# DB_Connectors.net
KiCad netlist of a schematic drawn in Altium Designer
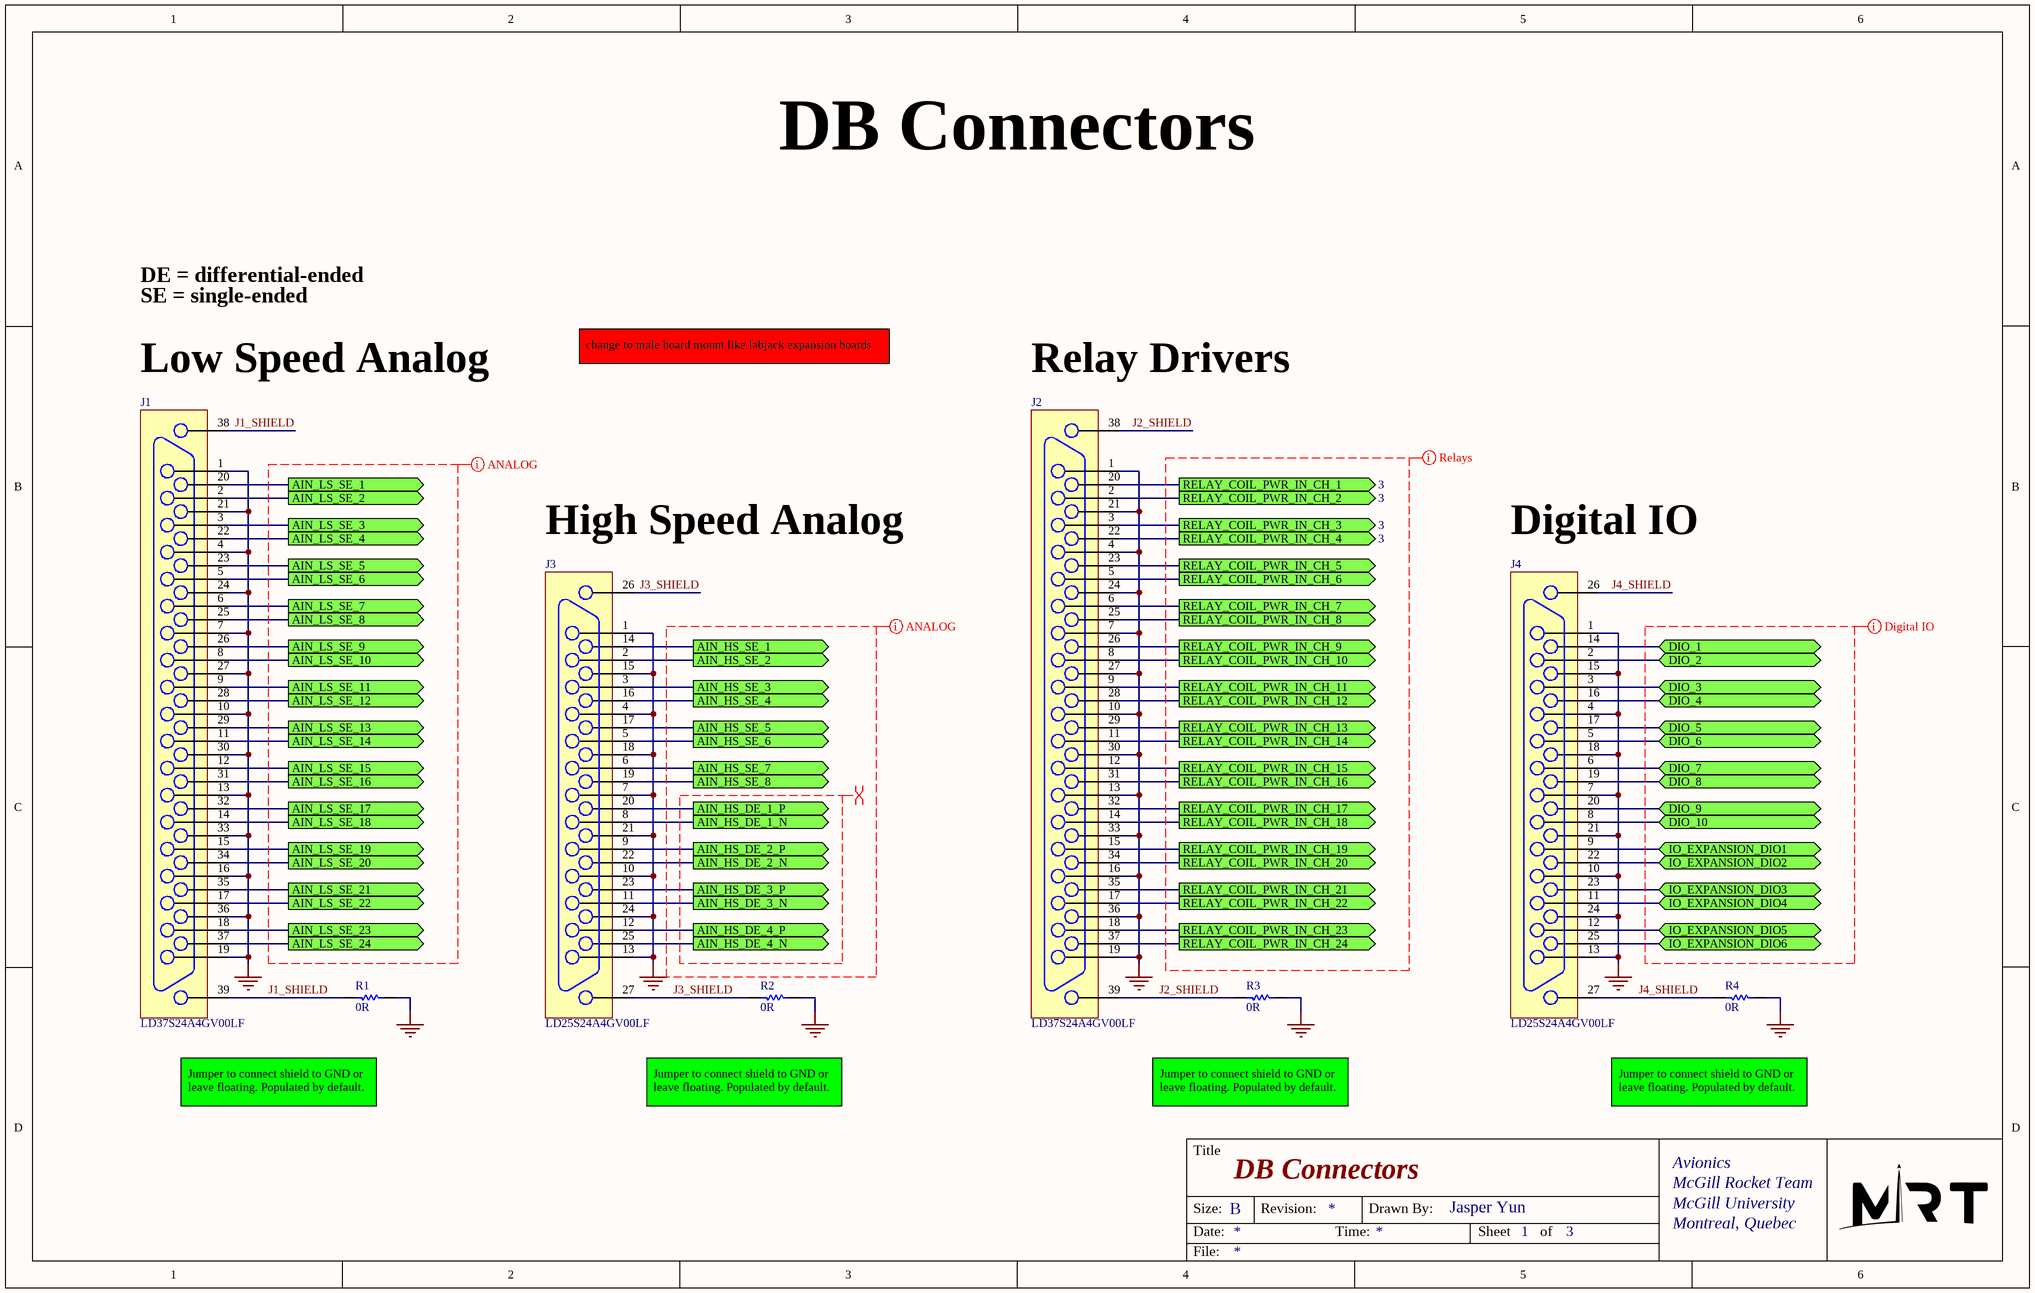
[diagram p0: DB Connectors.SchDoc]

(export (version "E")
  (design (tool "Eeschema 10.0.6"))
  (components
    (comp (ref "J1")
      (value "LD37S24A4GV00LF")
      (footprint "Connector DB37 Vertical LD37S24A4GV00LF")
      (description "DB37 LD37S24A4GV00LF (Amphenol ICC)")
      (libsource (lib "MRT SCH Library") (part "Connector DB37 (LD37S24A4GV00LF)"))
    )
    (comp (ref "J2")
      (value "LD37S24A4GV00LF")
      (footprint "Connector DB37 Vertical LD37S24A4GV00LF")
      (description "DB37 LD37S24A4GV00LF (Amphenol ICC)")
      (libsource (lib "MRT SCH Library") (part "Connector DB37 (LD37S24A4GV00LF)"))
    )
    (comp (ref "J3")
      (value "LD25S24A4GV00LF")
      (footprint "Connector DB25 Vertical LD25S24A4GV00LF")
      (description "DB25 LD25S24A4GV00LF (Amphenol ICC)")
      (libsource (lib "MRT SCH Library") (part "Connector DB25 (LD25S24A4GV00LF)"))
    )
    (comp (ref "J4")
      (value "LD25S24A4GV00LF")
      (footprint "Connector DB25 Vertical LD25S24A4GV00LF")
      (description "DB25 LD25S24A4GV00LF (Amphenol ICC)")
      (libsource (lib "MRT SCH Library") (part "Connector DB25 (LD25S24A4GV00LF)"))
    )
    (comp (ref "R1")
      (value "0R")
      (footprint "0402 RES")
      (description "Resistor")
      (fields (field (name "PUBLISHER") "Altium Limited"))
      (libsource (lib "Miscellaneous Devices") (part "Res1"))
    )
    (comp (ref "R2")
      (value "0R")
      (footprint "0402 RES")
      (description "Resistor")
      (fields (field (name "PUBLISHER") "Altium Limited"))
      (libsource (lib "Miscellaneous Devices") (part "Res1"))
    )
    (comp (ref "R3")
      (value "0R")
      (footprint "0402 RES")
      (description "Resistor")
      (fields (field (name "PUBLISHER") "Altium Limited"))
      (libsource (lib "Miscellaneous Devices") (part "Res1"))
    )
    (comp (ref "R4")
      (value "0R")
      (footprint "0402 RES")
      (description "Resistor")
      (fields (field (name "PUBLISHER") "Altium Limited"))
      (libsource (lib "Miscellaneous Devices") (part "Res1"))
    )
  )
  (nets
    (net (code "1") (name "/AIN_HS_DE_1_N") (class "Default")
      (node (ref "J3") (pin "8") (pinfunction "8_8") (pintype "passive"))
    )
    (net (code "2") (name "/AIN_HS_DE_1_P") (class "Default")
      (node (ref "J3") (pin "20") (pinfunction "20_20") (pintype "passive"))
    )
    (net (code "3") (name "/AIN_HS_DE_2_N") (class "Default")
      (node (ref "J3") (pin "22") (pinfunction "22_22") (pintype "passive"))
    )
    (net (code "4") (name "/AIN_HS_DE_2_P") (class "Default")
      (node (ref "J3") (pin "9") (pinfunction "9_9") (pintype "passive"))
    )
    (net (code "5") (name "/AIN_HS_DE_3_N") (class "Default")
      (node (ref "J3") (pin "11") (pinfunction "11_11") (pintype "passive"))
    )
    (net (code "6") (name "/AIN_HS_DE_3_P") (class "Default")
      (node (ref "J3") (pin "23") (pinfunction "23_23") (pintype "passive"))
    )
    (net (code "7") (name "/AIN_HS_DE_4_N") (class "Default")
      (node (ref "J3") (pin "25") (pinfunction "25_25") (pintype "passive"))
    )
    (net (code "8") (name "/AIN_HS_DE_4_P") (class "Default")
      (node (ref "J3") (pin "12") (pinfunction "12_12") (pintype "passive"))
    )
    (net (code "9") (name "/AIN_HS_SE_1") (class "Default")
      (node (ref "J3") (pin "14") (pinfunction "14_14") (pintype "passive"))
    )
    (net (code "10") (name "/AIN_HS_SE_2") (class "Default")
      (node (ref "J3") (pin "2") (pinfunction "2_2") (pintype "passive"))
    )
    (net (code "11") (name "/AIN_HS_SE_3") (class "Default")
      (node (ref "J3") (pin "3") (pinfunction "3_3") (pintype "passive"))
    )
    (net (code "12") (name "/AIN_HS_SE_4") (class "Default")
      (node (ref "J3") (pin "16") (pinfunction "16_16") (pintype "passive"))
    )
    (net (code "13") (name "/AIN_HS_SE_5") (class "Default")
      (node (ref "J3") (pin "17") (pinfunction "17_17") (pintype "passive"))
    )
    (net (code "14") (name "/AIN_HS_SE_6") (class "Default")
      (node (ref "J3") (pin "5") (pinfunction "5_5") (pintype "passive"))
    )
    (net (code "15") (name "/AIN_HS_SE_7") (class "Default")
      (node (ref "J3") (pin "6") (pinfunction "6_6") (pintype "passive"))
    )
    (net (code "16") (name "/AIN_HS_SE_8") (class "Default")
      (node (ref "J3") (pin "19") (pinfunction "19_19") (pintype "passive"))
    )
    (net (code "17") (name "/AIN_LS_SE_1") (class "Default")
      (node (ref "J1") (pin "20") (pinfunction "20_20") (pintype "passive"))
    )
    (net (code "18") (name "/AIN_LS_SE_2") (class "Default")
      (node (ref "J1") (pin "2") (pinfunction "2_2") (pintype "passive"))
    )
    (net (code "19") (name "/AIN_LS_SE_3") (class "Default")
      (node (ref "J1") (pin "3") (pinfunction "3_3") (pintype "passive"))
    )
    (net (code "20") (name "/AIN_LS_SE_4") (class "Default")
      (node (ref "J1") (pin "22") (pinfunction "22_22") (pintype "passive"))
    )
    (net (code "21") (name "/AIN_LS_SE_5") (class "Default")
      (node (ref "J1") (pin "23") (pinfunction "23_23") (pintype "passive"))
    )
    (net (code "22") (name "/AIN_LS_SE_6") (class "Default")
      (node (ref "J1") (pin "5") (pinfunction "5_5") (pintype "passive"))
    )
    (net (code "23") (name "/AIN_LS_SE_7") (class "Default")
      (node (ref "J1") (pin "6") (pinfunction "6_6") (pintype "passive"))
    )
    (net (code "24") (name "/AIN_LS_SE_8") (class "Default")
      (node (ref "J1") (pin "25") (pinfunction "25_25") (pintype "passive"))
    )
    (net (code "25") (name "/AIN_LS_SE_9") (class "Default")
      (node (ref "J1") (pin "26") (pinfunction "26_26") (pintype "passive"))
    )
    (net (code "26") (name "/AIN_LS_SE_10") (class "Default")
      (node (ref "J1") (pin "8") (pinfunction "8_8") (pintype "passive"))
    )
    (net (code "27") (name "/AIN_LS_SE_11") (class "Default")
      (node (ref "J1") (pin "9") (pinfunction "9_9") (pintype "passive"))
    )
    (net (code "28") (name "/AIN_LS_SE_12") (class "Default")
      (node (ref "J1") (pin "28") (pinfunction "28_28") (pintype "passive"))
    )
    (net (code "29") (name "/AIN_LS_SE_13") (class "Default")
      (node (ref "J1") (pin "29") (pinfunction "29_29") (pintype "passive"))
    )
    (net (code "30") (name "/AIN_LS_SE_14") (class "Default")
      (node (ref "J1") (pin "11") (pinfunction "11_11") (pintype "passive"))
    )
    (net (code "31") (name "/AIN_LS_SE_15") (class "Default")
      (node (ref "J1") (pin "12") (pinfunction "12_12") (pintype "passive"))
    )
    (net (code "32") (name "/AIN_LS_SE_16") (class "Default")
      (node (ref "J1") (pin "31") (pinfunction "31_31") (pintype "passive"))
    )
    (net (code "33") (name "/AIN_LS_SE_17") (class "Default")
      (node (ref "J1") (pin "32") (pinfunction "32_32") (pintype "passive"))
    )
    (net (code "34") (name "/AIN_LS_SE_18") (class "Default")
      (node (ref "J1") (pin "14") (pinfunction "14_14") (pintype "passive"))
    )
    (net (code "35") (name "/AIN_LS_SE_19") (class "Default")
      (node (ref "J1") (pin "15") (pinfunction "15_15") (pintype "passive"))
    )
    (net (code "36") (name "/AIN_LS_SE_20") (class "Default")
      (node (ref "J1") (pin "34") (pinfunction "34_34") (pintype "passive"))
    )
    (net (code "37") (name "/AIN_LS_SE_21") (class "Default")
      (node (ref "J1") (pin "35") (pinfunction "35_35") (pintype "passive"))
    )
    (net (code "38") (name "/AIN_LS_SE_22") (class "Default")
      (node (ref "J1") (pin "17") (pinfunction "17_17") (pintype "passive"))
    )
    (net (code "39") (name "/AIN_LS_SE_23") (class "Default")
      (node (ref "J1") (pin "18") (pinfunction "18_18") (pintype "passive"))
    )
    (net (code "40") (name "/AIN_LS_SE_24") (class "Default")
      (node (ref "J1") (pin "37") (pinfunction "37_37") (pintype "passive"))
    )
    (net (code "41") (name "/DIO_1") (class "Default")
      (node (ref "J4") (pin "14") (pinfunction "14_14") (pintype "passive"))
    )
    (net (code "42") (name "/DIO_2") (class "Default")
      (node (ref "J4") (pin "2") (pinfunction "2_2") (pintype "passive"))
    )
    (net (code "43") (name "/DIO_3") (class "Default")
      (node (ref "J4") (pin "3") (pinfunction "3_3") (pintype "passive"))
    )
    (net (code "44") (name "/DIO_4") (class "Default")
      (node (ref "J4") (pin "16") (pinfunction "16_16") (pintype "passive"))
    )
    (net (code "45") (name "/DIO_5") (class "Default")
      (node (ref "J4") (pin "17") (pinfunction "17_17") (pintype "passive"))
    )
    (net (code "46") (name "/DIO_6") (class "Default")
      (node (ref "J4") (pin "5") (pinfunction "5_5") (pintype "passive"))
    )
    (net (code "47") (name "/DIO_7") (class "Default")
      (node (ref "J4") (pin "6") (pinfunction "6_6") (pintype "passive"))
    )
    (net (code "48") (name "/DIO_8") (class "Default")
      (node (ref "J4") (pin "19") (pinfunction "19_19") (pintype "passive"))
    )
    (net (code "49") (name "/DIO_9") (class "Default")
      (node (ref "J4") (pin "20") (pinfunction "20_20") (pintype "passive"))
    )
    (net (code "50") (name "/DIO_10") (class "Default")
      (node (ref "J4") (pin "8") (pinfunction "8_8") (pintype "passive"))
    )
    (net (code "51") (name "/IO_EXPANSION_DIO1") (class "Default")
      (node (ref "J4") (pin "9") (pinfunction "9_9") (pintype "passive"))
    )
    (net (code "52") (name "/IO_EXPANSION_DIO2") (class "Default")
      (node (ref "J4") (pin "22") (pinfunction "22_22") (pintype "passive"))
    )
    (net (code "53") (name "/IO_EXPANSION_DIO3") (class "Default")
      (node (ref "J4") (pin "23") (pinfunction "23_23") (pintype "passive"))
    )
    (net (code "54") (name "/IO_EXPANSION_DIO4") (class "Default")
      (node (ref "J4") (pin "11") (pinfunction "11_11") (pintype "passive"))
    )
    (net (code "55") (name "/IO_EXPANSION_DIO5") (class "Default")
      (node (ref "J4") (pin "12") (pinfunction "12_12") (pintype "passive"))
    )
    (net (code "56") (name "/IO_EXPANSION_DIO6") (class "Default")
      (node (ref "J4") (pin "25") (pinfunction "25_25") (pintype "passive"))
    )
    (net (code "57") (name "/J1_SHIELD") (class "Default")
      (node (ref "J1") (pin "38") (pinfunction "38_38") (pintype "passive"))
      (node (ref "J1") (pin "39") (pinfunction "39_39") (pintype "passive"))
      (node (ref "R1") (pin "1") (pinfunction "1_1") (pintype "passive"))
    )
    (net (code "58") (name "/J2_SHIELD") (class "Default")
      (node (ref "J2") (pin "38") (pinfunction "38_38") (pintype "passive"))
      (node (ref "J2") (pin "39") (pinfunction "39_39") (pintype "passive"))
      (node (ref "R3") (pin "1") (pinfunction "1_1") (pintype "passive"))
    )
    (net (code "59") (name "/J3_SHIELD") (class "Default")
      (node (ref "J3") (pin "26") (pinfunction "26_26") (pintype "passive"))
      (node (ref "J3") (pin "27") (pinfunction "27_27") (pintype "passive"))
      (node (ref "R2") (pin "1") (pinfunction "1_1") (pintype "passive"))
    )
    (net (code "60") (name "/J4_SHIELD") (class "Default")
      (node (ref "J4") (pin "26") (pinfunction "26_26") (pintype "passive"))
      (node (ref "J4") (pin "27") (pinfunction "27_27") (pintype "passive"))
      (node (ref "R4") (pin "1") (pinfunction "1_1") (pintype "passive"))
    )
    (net (code "61") (name "/RELAY_COIL_PWR_IN_CH_1") (class "Default")
      (node (ref "J2") (pin "20") (pinfunction "20_20") (pintype "passive"))
    )
    (net (code "62") (name "/RELAY_COIL_PWR_IN_CH_2") (class "Default")
      (node (ref "J2") (pin "2") (pinfunction "2_2") (pintype "passive"))
    )
    (net (code "63") (name "/RELAY_COIL_PWR_IN_CH_3") (class "Default")
      (node (ref "J2") (pin "3") (pinfunction "3_3") (pintype "passive"))
    )
    (net (code "64") (name "/RELAY_COIL_PWR_IN_CH_4") (class "Default")
      (node (ref "J2") (pin "22") (pinfunction "22_22") (pintype "passive"))
    )
    (net (code "65") (name "/RELAY_COIL_PWR_IN_CH_5") (class "Default")
      (node (ref "J2") (pin "23") (pinfunction "23_23") (pintype "passive"))
    )
    (net (code "66") (name "/RELAY_COIL_PWR_IN_CH_6") (class "Default")
      (node (ref "J2") (pin "5") (pinfunction "5_5") (pintype "passive"))
    )
    (net (code "67") (name "/RELAY_COIL_PWR_IN_CH_7") (class "Default")
      (node (ref "J2") (pin "6") (pinfunction "6_6") (pintype "passive"))
    )
    (net (code "68") (name "/RELAY_COIL_PWR_IN_CH_8") (class "Default")
      (node (ref "J2") (pin "25") (pinfunction "25_25") (pintype "passive"))
    )
    (net (code "69") (name "/RELAY_COIL_PWR_IN_CH_9") (class "Default")
      (node (ref "J2") (pin "26") (pinfunction "26_26") (pintype "passive"))
    )
    (net (code "70") (name "/RELAY_COIL_PWR_IN_CH_10") (class "Default")
      (node (ref "J2") (pin "8") (pinfunction "8_8") (pintype "passive"))
    )
    (net (code "71") (name "/RELAY_COIL_PWR_IN_CH_11") (class "Default")
      (node (ref "J2") (pin "9") (pinfunction "9_9") (pintype "passive"))
    )
    (net (code "72") (name "/RELAY_COIL_PWR_IN_CH_12") (class "Default")
      (node (ref "J2") (pin "28") (pinfunction "28_28") (pintype "passive"))
    )
    (net (code "73") (name "/RELAY_COIL_PWR_IN_CH_13") (class "Default")
      (node (ref "J2") (pin "29") (pinfunction "29_29") (pintype "passive"))
    )
    (net (code "74") (name "/RELAY_COIL_PWR_IN_CH_14") (class "Default")
      (node (ref "J2") (pin "11") (pinfunction "11_11") (pintype "passive"))
    )
    (net (code "75") (name "/RELAY_COIL_PWR_IN_CH_15") (class "Default")
      (node (ref "J2") (pin "12") (pinfunction "12_12") (pintype "passive"))
    )
    (net (code "76") (name "/RELAY_COIL_PWR_IN_CH_16") (class "Default")
      (node (ref "J2") (pin "31") (pinfunction "31_31") (pintype "passive"))
    )
    (net (code "77") (name "/RELAY_COIL_PWR_IN_CH_17") (class "Default")
      (node (ref "J2") (pin "32") (pinfunction "32_32") (pintype "passive"))
    )
    (net (code "78") (name "/RELAY_COIL_PWR_IN_CH_18") (class "Default")
      (node (ref "J2") (pin "14") (pinfunction "14_14") (pintype "passive"))
    )
    (net (code "79") (name "/RELAY_COIL_PWR_IN_CH_19") (class "Default")
      (node (ref "J2") (pin "15") (pinfunction "15_15") (pintype "passive"))
    )
    (net (code "80") (name "/RELAY_COIL_PWR_IN_CH_20") (class "Default")
      (node (ref "J2") (pin "34") (pinfunction "34_34") (pintype "passive"))
    )
    (net (code "81") (name "/RELAY_COIL_PWR_IN_CH_21") (class "Default")
      (node (ref "J2") (pin "35") (pinfunction "35_35") (pintype "passive"))
    )
    (net (code "82") (name "/RELAY_COIL_PWR_IN_CH_22") (class "Default")
      (node (ref "J2") (pin "17") (pinfunction "17_17") (pintype "passive"))
    )
    (net (code "83") (name "/RELAY_COIL_PWR_IN_CH_23") (class "Default")
      (node (ref "J2") (pin "18") (pinfunction "18_18") (pintype "passive"))
    )
    (net (code "84") (name "/RELAY_COIL_PWR_IN_CH_24") (class "Default")
      (node (ref "J2") (pin "37") (pinfunction "37_37") (pintype "passive"))
    )
    (net (code "85") (name "GND") (class "Default")
      (node (ref "J1") (pin "1") (pinfunction "1_1") (pintype "passive"))
      (node (ref "J1") (pin "10") (pinfunction "10_10") (pintype "passive"))
      (node (ref "J1") (pin "13") (pinfunction "13_13") (pintype "passive"))
      (node (ref "J1") (pin "16") (pinfunction "16_16") (pintype "passive"))
      (node (ref "J1") (pin "19") (pinfunction "19_19") (pintype "passive"))
      (node (ref "J1") (pin "21") (pinfunction "21_21") (pintype "passive"))
      (node (ref "J1") (pin "24") (pinfunction "24_24") (pintype "passive"))
      (node (ref "J1") (pin "27") (pinfunction "27_27") (pintype "passive"))
      (node (ref "J1") (pin "30") (pinfunction "30_30") (pintype "passive"))
      (node (ref "J1") (pin "33") (pinfunction "33_33") (pintype "passive"))
      (node (ref "J1") (pin "36") (pinfunction "36_36") (pintype "passive"))
      (node (ref "J1") (pin "4") (pinfunction "4_4") (pintype "passive"))
      (node (ref "J1") (pin "7") (pinfunction "7_7") (pintype "passive"))
      (node (ref "J2") (pin "1") (pinfunction "1_1") (pintype "passive"))
      (node (ref "J2") (pin "10") (pinfunction "10_10") (pintype "passive"))
      (node (ref "J2") (pin "13") (pinfunction "13_13") (pintype "passive"))
      (node (ref "J2") (pin "16") (pinfunction "16_16") (pintype "passive"))
      (node (ref "J2") (pin "19") (pinfunction "19_19") (pintype "passive"))
      (node (ref "J2") (pin "21") (pinfunction "21_21") (pintype "passive"))
      (node (ref "J2") (pin "24") (pinfunction "24_24") (pintype "passive"))
      (node (ref "J2") (pin "27") (pinfunction "27_27") (pintype "passive"))
      (node (ref "J2") (pin "30") (pinfunction "30_30") (pintype "passive"))
      (node (ref "J2") (pin "33") (pinfunction "33_33") (pintype "passive"))
      (node (ref "J2") (pin "36") (pinfunction "36_36") (pintype "passive"))
      (node (ref "J2") (pin "4") (pinfunction "4_4") (pintype "passive"))
      (node (ref "J2") (pin "7") (pinfunction "7_7") (pintype "passive"))
      (node (ref "J3") (pin "1") (pinfunction "1_1") (pintype "passive"))
      (node (ref "J3") (pin "10") (pinfunction "10_10") (pintype "passive"))
      (node (ref "J3") (pin "13") (pinfunction "13_13") (pintype "passive"))
      (node (ref "J3") (pin "15") (pinfunction "15_15") (pintype "passive"))
      (node (ref "J3") (pin "18") (pinfunction "18_18") (pintype "passive"))
      (node (ref "J3") (pin "21") (pinfunction "21_21") (pintype "passive"))
      (node (ref "J3") (pin "24") (pinfunction "24_24") (pintype "passive"))
      (node (ref "J3") (pin "4") (pinfunction "4_4") (pintype "passive"))
      (node (ref "J3") (pin "7") (pinfunction "7_7") (pintype "passive"))
      (node (ref "J4") (pin "1") (pinfunction "1_1") (pintype "passive"))
      (node (ref "J4") (pin "10") (pinfunction "10_10") (pintype "passive"))
      (node (ref "J4") (pin "13") (pinfunction "13_13") (pintype "passive"))
      (node (ref "J4") (pin "15") (pinfunction "15_15") (pintype "passive"))
      (node (ref "J4") (pin "18") (pinfunction "18_18") (pintype "passive"))
      (node (ref "J4") (pin "21") (pinfunction "21_21") (pintype "passive"))
      (node (ref "J4") (pin "24") (pinfunction "24_24") (pintype "passive"))
      (node (ref "J4") (pin "4") (pinfunction "4_4") (pintype "passive"))
      (node (ref "J4") (pin "7") (pinfunction "7_7") (pintype "passive"))
      (node (ref "R1") (pin "2") (pinfunction "2_2") (pintype "passive"))
      (node (ref "R2") (pin "2") (pinfunction "2_2") (pintype "passive"))
      (node (ref "R3") (pin "2") (pinfunction "2_2") (pintype "passive"))
      (node (ref "R4") (pin "2") (pinfunction "2_2") (pintype "passive"))
    )
  )
)
